# Weather_Shield_V12.net
KiCad netlist of a schematic drawn in EAGLE
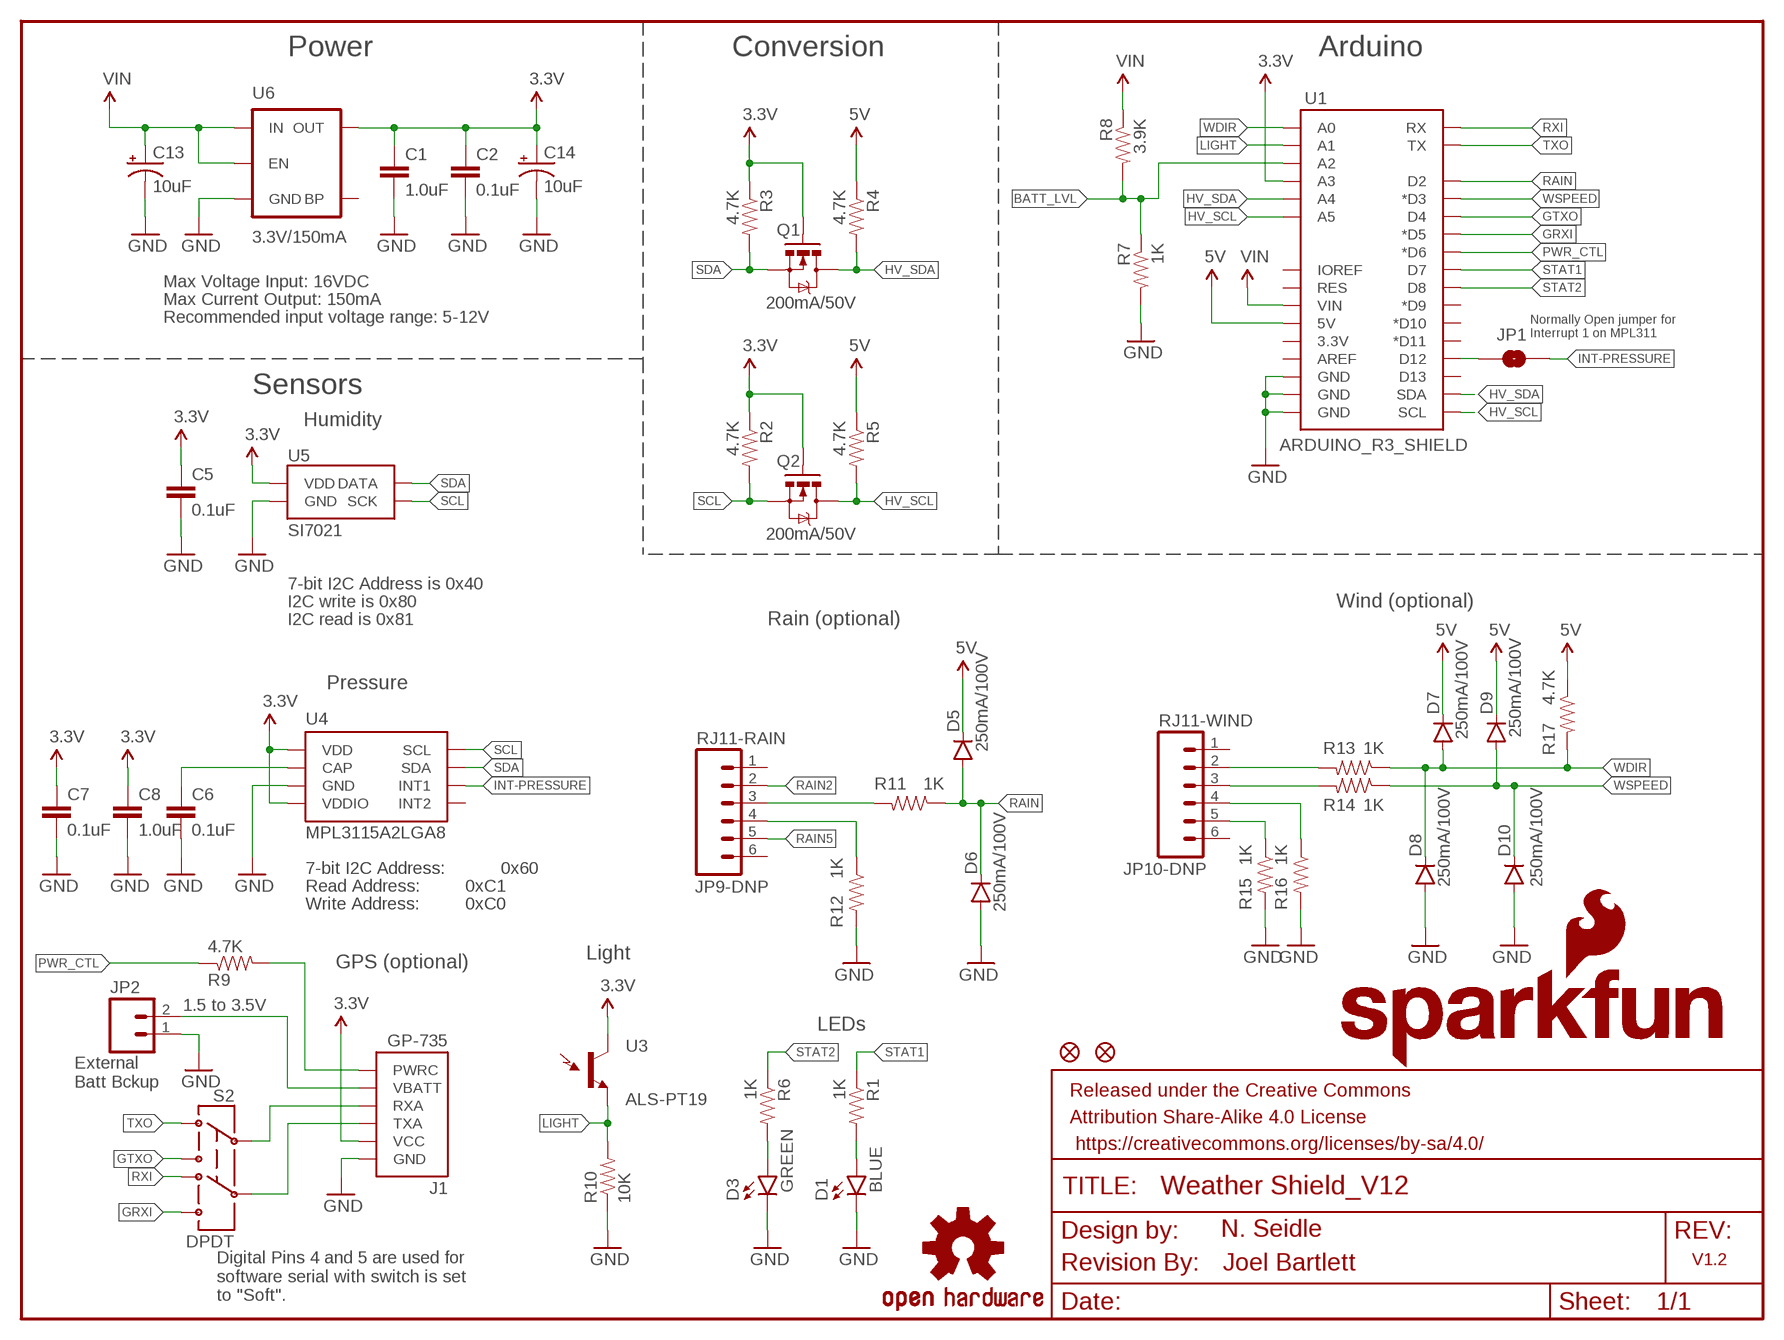
[diagram p0: schematic, sheet 1]

(export (version "E")
  (design (tool "Eeschema 10.0.6"))
  (components
    (comp (ref "C1")
      (value "1.0uF")
      (footprint "eagle-import:0603-CAP")
      (libsource (lib "eagle-import") (part "1.0UF-16V-10%(0603)"))
    )
    (comp (ref "C2")
      (value "0.1uF")
      (footprint "eagle-import:0603-CAP")
      (libsource (lib "eagle-import") (part "0.1UF-25V(+80/-20%)(0603)"))
    )
    (comp (ref "C5")
      (value "0.1uF")
      (footprint "eagle-import:0603-CAP")
      (libsource (lib "eagle-import") (part "0.1UF-25V(+80/-20%)(0603)"))
    )
    (comp (ref "C6")
      (value "0.1uF")
      (footprint "eagle-import:0603-CAP")
      (libsource (lib "eagle-import") (part "0.1UF-25V(+80/-20%)(0603)"))
    )
    (comp (ref "C7")
      (value "0.1uF")
      (footprint "eagle-import:0603-CAP")
      (libsource (lib "eagle-import") (part "0.1UF-25V(+80/-20%)(0603)"))
    )
    (comp (ref "C8")
      (value "1.0uF")
      (footprint "eagle-import:0603-CAP")
      (libsource (lib "eagle-import") (part "1.0UF-16V-10%(0603)"))
    )
    (comp (ref "C13")
      (value "10uF")
      (footprint "eagle-import:EIA3216")
      (libsource (lib "eagle-import") (part "10UF-16V-10%(TANT)"))
    )
    (comp (ref "C14")
      (value "10uF")
      (footprint "eagle-import:EIA3216")
      (libsource (lib "eagle-import") (part "10UF-16V-10%(TANT)"))
    )
    (comp (ref "D1")
      (value "BLUE")
      (footprint "eagle-import:LED-0603")
      (libsource (lib "eagle-import") (part "LED-BLUE0603"))
    )
    (comp (ref "D3")
      (value "GREEN")
      (footprint "eagle-import:LED-0603")
      (libsource (lib "eagle-import") (part "LED-GREEN0603"))
    )
    (comp (ref "D5")
      (value "250mA/100V")
      (footprint "eagle-import:SOD-323")
      (libsource (lib "eagle-import") (part "DIODEBAS16"))
    )
    (comp (ref "D6")
      (value "250mA/100V")
      (footprint "eagle-import:SOD-323")
      (libsource (lib "eagle-import") (part "DIODEBAS16"))
    )
    (comp (ref "D7")
      (value "250mA/100V")
      (footprint "eagle-import:SOD-323")
      (libsource (lib "eagle-import") (part "DIODEBAS16"))
    )
    (comp (ref "D8")
      (value "250mA/100V")
      (footprint "eagle-import:SOD-323")
      (libsource (lib "eagle-import") (part "DIODEBAS16"))
    )
    (comp (ref "D9")
      (value "250mA/100V")
      (footprint "eagle-import:SOD-323")
      (libsource (lib "eagle-import") (part "DIODEBAS16"))
    )
    (comp (ref "D10")
      (value "250mA/100V")
      (footprint "eagle-import:SOD-323")
      (libsource (lib "eagle-import") (part "DIODEBAS16"))
    )
    (comp (ref "FD1")
      (value "FIDUCIAL1X2")
      (footprint "eagle-import:FIDUCIAL-1X2")
      (libsource (lib "eagle-import") (part "FIDUCIAL1X2"))
    )
    (comp (ref "FD2")
      (value "FIDUCIAL1X2")
      (footprint "eagle-import:FIDUCIAL-1X2")
      (libsource (lib "eagle-import") (part "FIDUCIAL1X2"))
    )
    (comp (ref "FRAME1")
      (value "FRAME-LETTER")
      (footprint "eagle-import:CREATIVE_COMMONS")
      (libsource (lib "eagle-import") (part "FRAME-LETTER"))
    )
    (comp (ref "J1")
      (value "GP-735")
      (footprint "eagle-import:GP-635T")
      (libsource (lib "eagle-import") (part "GP-635TSMD"))
    )
    (comp (ref "JP1")
      (value "JUMPER-PAD-2-NO")
      (footprint "eagle-import:PAD-JUMPER-2-NO_NO_SILK")
      (libsource (lib "eagle-import") (part "JUMPER-PAD-2-NO"))
    )
    (comp (ref "JP2")
      (value "External Batt Bckup")
      (footprint "eagle-import:1X02")
      (libsource (lib "eagle-import") (part "M02PTH"))
    )
    (comp (ref "JP9-DNP")
      (value "RJ11-RAIN")
      (footprint "eagle-import:RJ11-6")
      (libsource (lib "eagle-import") (part "RJ11-6PTH"))
    )
    (comp (ref "JP10-DNP")
      (value "RJ11-WIND")
      (footprint "eagle-import:RJ11-6")
      (libsource (lib "eagle-import") (part "RJ11-6PTH"))
    )
    (comp (ref "LOGO1")
      (value "OSHW-LOGOM")
      (footprint "eagle-import:OSHW-LOGO-M")
      (libsource (lib "eagle-import") (part "OSHW-LOGOM"))
    )
    (comp (ref "LOGO2")
      (value "SFE_LOGO_NAME_FLAME.1_INCH")
      (footprint "eagle-import:SFE_LOGO_NAME_FLAME_.1")
      (libsource (lib "eagle-import") (part "SFE_LOGO_NAME_FLAME.1_INCH"))
    )
    (comp (ref "Q1")
      (value "200mA/50V")
      (footprint "eagle-import:SOT23-3")
      (libsource (lib "eagle-import") (part "MOSFET-NCHANNELBSS138"))
    )
    (comp (ref "Q2")
      (value "200mA/50V")
      (footprint "eagle-import:SOT23-3")
      (libsource (lib "eagle-import") (part "MOSFET-NCHANNELBSS138"))
    )
    (comp (ref "R1")
      (value "1K")
      (footprint "eagle-import:0603-RES")
      (libsource (lib "eagle-import") (part "1KOHM-1/10W-1%(0603)"))
    )
    (comp (ref "R2")
      (value "4.7K")
      (footprint "eagle-import:0603-RES")
      (libsource (lib "eagle-import") (part "4.7KOHM-1/10W-1%(0603)"))
    )
    (comp (ref "R3")
      (value "4.7K")
      (footprint "eagle-import:0603-RES")
      (libsource (lib "eagle-import") (part "4.7KOHM-1/10W-1%(0603)"))
    )
    (comp (ref "R4")
      (value "4.7K")
      (footprint "eagle-import:0603-RES")
      (libsource (lib "eagle-import") (part "4.7KOHM-1/10W-1%(0603)"))
    )
    (comp (ref "R5")
      (value "4.7K")
      (footprint "eagle-import:0603-RES")
      (libsource (lib "eagle-import") (part "4.7KOHM-1/10W-1%(0603)"))
    )
    (comp (ref "R6")
      (value "1K")
      (footprint "eagle-import:0603-RES")
      (libsource (lib "eagle-import") (part "1KOHM-1/10W-1%(0603)"))
    )
    (comp (ref "R7")
      (value "1K")
      (footprint "eagle-import:0603-RES")
      (libsource (lib "eagle-import") (part "1KOHM-1/10W-1%(0603)"))
    )
    (comp (ref "R8")
      (value "3.9K")
      (footprint "eagle-import:0603")
      (libsource (lib "eagle-import") (part "3.9KOHM1/10W1%(0603)"))
    )
    (comp (ref "R9")
      (value "4.7K")
      (footprint "eagle-import:0603-RES")
      (libsource (lib "eagle-import") (part "4.7KOHM-1/10W-1%(0603)"))
    )
    (comp (ref "R10")
      (value "10K")
      (footprint "eagle-import:0603-RES")
      (libsource (lib "eagle-import") (part "10KOHM-1/10W-1%(0603)0603"))
    )
    (comp (ref "R11")
      (value "1K")
      (footprint "eagle-import:0603-RES")
      (libsource (lib "eagle-import") (part "1KOHM-1/10W-1%(0603)"))
    )
    (comp (ref "R12")
      (value "1K")
      (footprint "eagle-import:0603-RES")
      (libsource (lib "eagle-import") (part "1KOHM-1/10W-1%(0603)"))
    )
    (comp (ref "R13")
      (value "1K")
      (footprint "eagle-import:0603-RES")
      (libsource (lib "eagle-import") (part "1KOHM-1/10W-1%(0603)"))
    )
    (comp (ref "R14")
      (value "1K")
      (footprint "eagle-import:0603-RES")
      (libsource (lib "eagle-import") (part "1KOHM-1/10W-1%(0603)"))
    )
    (comp (ref "R15")
      (value "1K")
      (footprint "eagle-import:0603-RES")
      (libsource (lib "eagle-import") (part "1KOHM-1/10W-1%(0603)"))
    )
    (comp (ref "R16")
      (value "1K")
      (footprint "eagle-import:0603-RES")
      (libsource (lib "eagle-import") (part "1KOHM-1/10W-1%(0603)"))
    )
    (comp (ref "R17")
      (value "4.7K")
      (footprint "eagle-import:0603-RES")
      (libsource (lib "eagle-import") (part "4.7KOHM-1/10W-1%(0603)"))
    )
    (comp (ref "S2")
      (value "DPDT")
      (footprint "eagle-import:AYZ0202")
      (libsource (lib "eagle-import") (part "SWITCH-DPDTAYZ0202"))
    )
    (comp (ref "U$2")
      (value "REVISION")
      (footprint "eagle-import:REVISION")
      (libsource (lib "eagle-import") (part "REVISION"))
    )
    (comp (ref "U1")
      (value "ARDUINO_R3_SHIELD")
      (footprint "eagle-import:UNO_R3_SHIELD")
      (libsource (lib "eagle-import") (part "ARDUINO_R3_SHIELD"))
    )
    (comp (ref "U3")
      (value "ALS-PT19")
      (footprint "eagle-import:ALS-PT19")
      (libsource (lib "eagle-import") (part "LIGHTSENSORALS"))
    )
    (comp (ref "U4")
      (value "MPL3115A2LGA8")
      (footprint "eagle-import:LGA8")
      (libsource (lib "eagle-import") (part "MPL3115A2LGA8"))
    )
    (comp (ref "U5")
      (value "SI7021")
      (footprint "eagle-import:SI7021")
      (libsource (lib "eagle-import") (part "SI7021"))
    )
    (comp (ref "U6")
      (value "3.3V/150mA")
      (footprint "eagle-import:SOT23-5")
      (libsource (lib "eagle-import") (part "V_REG_MIC52053.3V"))
    )
  )
  (nets
    (net (code "1") (name "3.3V") (class "Default")
      (node (ref "C1") (pin "1") (pinfunction "1_1") (pintype "passive"))
      (node (ref "C14") (pin "A") (pinfunction "+_A") (pintype "passive"))
      (node (ref "C2") (pin "1") (pinfunction "1_1") (pintype "passive"))
      (node (ref "C5") (pin "1") (pinfunction "1_1") (pintype "passive"))
      (node (ref "C7") (pin "1") (pinfunction "1_1") (pintype "passive"))
      (node (ref "C8") (pin "1") (pinfunction "1_1") (pintype "passive"))
      (node (ref "J1") (pin "2") (pinfunction "VCC_2") (pintype "power_in"))
      (node (ref "Q1") (pin "1") (pinfunction "G_1") (pintype "passive"))
      (node (ref "Q2") (pin "1") (pinfunction "G_1") (pintype "passive"))
      (node (ref "R2") (pin "1") (pinfunction "1_1") (pintype "passive"))
      (node (ref "R3") (pin "1") (pinfunction "1_1") (pintype "passive"))
      (node (ref "U1") (pin "A3") (pinfunction "A3_A3") (pintype "bidirectional"))
      (node (ref "U3") (pin "C") (pinfunction "C1_C") (pintype "passive"))
      (node (ref "U4") (pin "1") (pinfunction "VDD_1") (pintype "power_in"))
      (node (ref "U4") (pin "4") (pinfunction "VDDIO_4") (pintype "power_in"))
      (node (ref "U5") (pin "VDD") (pinfunction "VDD_VDD") (pintype "power_in"))
      (node (ref "U6") (pin "5") (pinfunction "OUT_5") (pintype "passive"))
    )
    (net (code "2") (name "5V") (class "Default")
      (node (ref "D5") (pin "C") (pinfunction "C_C") (pintype "passive"))
      (node (ref "D7") (pin "C") (pinfunction "C_C") (pintype "passive"))
      (node (ref "D9") (pin "C") (pinfunction "C_C") (pintype "passive"))
      (node (ref "R17") (pin "1") (pinfunction "1_1") (pintype "passive"))
      (node (ref "R4") (pin "1") (pinfunction "1_1") (pintype "passive"))
      (node (ref "R5") (pin "1") (pinfunction "1_1") (pintype "passive"))
      (node (ref "U1") (pin "5V") (pinfunction "5V_5V") (pintype "bidirectional"))
    )
    (net (code "3") (name "BATT_LVL") (class "Default")
      (node (ref "R7") (pin "1") (pinfunction "1_1") (pintype "passive"))
      (node (ref "R8") (pin "2") (pinfunction "2_2") (pintype "passive"))
      (node (ref "U1") (pin "A2") (pinfunction "A2_A2") (pintype "bidirectional"))
    )
    (net (code "4") (name "GND") (class "Default")
      (node (ref "C1") (pin "2") (pinfunction "2_2") (pintype "passive"))
      (node (ref "C13") (pin "C") (pinfunction "-_C") (pintype "passive"))
      (node (ref "C14") (pin "C") (pinfunction "-_C") (pintype "passive"))
      (node (ref "C2") (pin "2") (pinfunction "2_2") (pintype "passive"))
      (node (ref "C5") (pin "2") (pinfunction "2_2") (pintype "passive"))
      (node (ref "C6") (pin "2") (pinfunction "2_2") (pintype "passive"))
      (node (ref "C7") (pin "2") (pinfunction "2_2") (pintype "passive"))
      (node (ref "C8") (pin "2") (pinfunction "2_2") (pintype "passive"))
      (node (ref "D1") (pin "C") (pinfunction "C_C") (pintype "passive"))
      (node (ref "D10") (pin "A") (pinfunction "A_A") (pintype "passive"))
      (node (ref "D3") (pin "C") (pinfunction "C_C") (pintype "passive"))
      (node (ref "D6") (pin "A") (pinfunction "A_A") (pintype "passive"))
      (node (ref "D8") (pin "A") (pinfunction "A_A") (pintype "passive"))
      (node (ref "J1") (pin "1") (pinfunction "GND_1") (pintype "power_in"))
      (node (ref "JP2") (pin "1") (pinfunction "1_1") (pintype "passive"))
      (node (ref "R10") (pin "1") (pinfunction "1_1") (pintype "passive"))
      (node (ref "R12") (pin "2") (pinfunction "2_2") (pintype "passive"))
      (node (ref "R15") (pin "2") (pinfunction "2_2") (pintype "passive"))
      (node (ref "R16") (pin "2") (pinfunction "2_2") (pintype "passive"))
      (node (ref "R7") (pin "2") (pinfunction "2_2") (pintype "passive"))
      (node (ref "U1") (pin "GND@0") (pinfunction "GND_GND@0") (pintype "bidirectional"))
      (node (ref "U1") (pin "GND@1") (pinfunction "GND_GND@1") (pintype "bidirectional"))
      (node (ref "U1") (pin "GND@2") (pinfunction "GND_GND@2") (pintype "bidirectional"))
      (node (ref "U4") (pin "3") (pinfunction "GND_3") (pintype "power_in"))
      (node (ref "U5") (pin "GND") (pinfunction "GND_GND") (pintype "power_in"))
      (node (ref "U6") (pin "2") (pinfunction "GND_2") (pintype "input"))
    )
    (net (code "5") (name "GRXI") (class "Default")
      (node (ref "S2") (pin "6") (pinfunction "6_6") (pintype "bidirectional"))
      (node (ref "U1") (pin "D5") (pinfunction "*D5_D5") (pintype "bidirectional"))
    )
    (net (code "6") (name "GTXO") (class "Default")
      (node (ref "S2") (pin "3") (pinfunction "3_3") (pintype "bidirectional"))
      (node (ref "U1") (pin "D4") (pinfunction "D4_D4") (pintype "bidirectional"))
    )
    (net (code "7") (name "HV_SCL") (class "Default")
      (node (ref "Q2") (pin "3") (pinfunction "D_3") (pintype "passive"))
      (node (ref "R5") (pin "2") (pinfunction "2_2") (pintype "passive"))
      (node (ref "U1") (pin "A5") (pinfunction "A5_A5") (pintype "bidirectional"))
      (node (ref "U1") (pin "SCL") (pinfunction "SCL_SCL") (pintype "bidirectional"))
    )
    (net (code "8") (name "HV_SDA") (class "Default")
      (node (ref "Q1") (pin "3") (pinfunction "D_3") (pintype "passive"))
      (node (ref "R4") (pin "2") (pinfunction "2_2") (pintype "passive"))
      (node (ref "U1") (pin "A4") (pinfunction "A4_A4") (pintype "bidirectional"))
      (node (ref "U1") (pin "SDA") (pinfunction "SDA_SDA") (pintype "bidirectional"))
    )
    (net (code "9") (name "INT-PRESSURE") (class "Default")
      (node (ref "JP1") (pin "2") (pinfunction "2_2") (pintype "passive"))
      (node (ref "U4") (pin "6") (pinfunction "INT1_6") (pintype "output"))
    )
    (net (code "10") (name "LIGHT") (class "Default")
      (node (ref "R10") (pin "2") (pinfunction "2_2") (pintype "passive"))
      (node (ref "U1") (pin "A1") (pinfunction "A1_A1") (pintype "bidirectional"))
      (node (ref "U3") (pin "E") (pinfunction "E1_E") (pintype "passive"))
    )
    (net (code "11") (name "Net-(D1-PadA)") (class "Default")
      (node (ref "D1") (pin "A") (pinfunction "A_A") (pintype "passive"))
      (node (ref "R1") (pin "2") (pinfunction "2_2") (pintype "passive"))
    )
    (net (code "12") (name "Net-(D3-PadA)") (class "Default")
      (node (ref "D3") (pin "A") (pinfunction "A_A") (pintype "passive"))
      (node (ref "R6") (pin "2") (pinfunction "2_2") (pintype "passive"))
    )
    (net (code "13") (name "Net-(J1-PWRC)") (class "Default")
      (node (ref "J1") (pin "6") (pinfunction "PWRC_6") (pintype "input"))
      (node (ref "R9") (pin "2") (pinfunction "2_2") (pintype "passive"))
    )
    (net (code "14") (name "Net-(J1-RXA)") (class "Default")
      (node (ref "J1") (pin "4") (pinfunction "RXA_4") (pintype "input"))
      (node (ref "S2") (pin "2") (pinfunction "2_2") (pintype "bidirectional"))
    )
    (net (code "15") (name "Net-(J1-TXA)") (class "Default")
      (node (ref "J1") (pin "3") (pinfunction "TXA_3") (pintype "output"))
      (node (ref "S2") (pin "5") (pinfunction "5_5") (pintype "bidirectional"))
    )
    (net (code "16") (name "Net-(J1-VBATT)") (class "Default")
      (node (ref "J1") (pin "5") (pinfunction "VBATT_5") (pintype "power_in"))
      (node (ref "JP2") (pin "2") (pinfunction "2_2") (pintype "passive"))
    )
    (net (code "17") (name "Net-(JP1-Pad1)") (class "Default")
      (node (ref "JP1") (pin "1") (pinfunction "1_1") (pintype "passive"))
      (node (ref "U1") (pin "D12") (pinfunction "D12_D12") (pintype "bidirectional"))
    )
    (net (code "18") (name "Net-(JP9-DNP-Pad3)") (class "Default")
      (node (ref "JP9-DNP") (pin "3") (pinfunction "3_3") (pintype "passive"))
      (node (ref "R11") (pin "2") (pinfunction "2_2") (pintype "passive"))
    )
    (net (code "19") (name "Net-(JP9-DNP-Pad4)") (class "Default")
      (node (ref "JP9-DNP") (pin "4") (pinfunction "4_4") (pintype "passive"))
      (node (ref "R12") (pin "1") (pinfunction "1_1") (pintype "passive"))
    )
    (net (code "20") (name "Net-(JP10-DNP-Pad2)") (class "Default")
      (node (ref "JP10-DNP") (pin "2") (pinfunction "2_2") (pintype "passive"))
      (node (ref "R13") (pin "2") (pinfunction "2_2") (pintype "passive"))
    )
    (net (code "21") (name "Net-(JP10-DNP-Pad3)") (class "Default")
      (node (ref "JP10-DNP") (pin "3") (pinfunction "3_3") (pintype "passive"))
      (node (ref "R14") (pin "2") (pinfunction "2_2") (pintype "passive"))
    )
    (net (code "22") (name "Net-(JP10-DNP-Pad4)") (class "Default")
      (node (ref "JP10-DNP") (pin "4") (pinfunction "4_4") (pintype "passive"))
      (node (ref "R16") (pin "1") (pinfunction "1_1") (pintype "passive"))
    )
    (net (code "23") (name "Net-(JP10-DNP-Pad5)") (class "Default")
      (node (ref "JP10-DNP") (pin "5") (pinfunction "5_5") (pintype "passive"))
      (node (ref "R15") (pin "1") (pinfunction "1_1") (pintype "passive"))
    )
    (net (code "24") (name "Net-(U4-CAP)") (class "Default")
      (node (ref "C6") (pin "1") (pinfunction "1_1") (pintype "passive"))
      (node (ref "U4") (pin "2") (pinfunction "CAP_2") (pintype "power_in"))
    )
    (net (code "25") (name "PWR_CTL") (class "Default")
      (node (ref "R9") (pin "1") (pinfunction "1_1") (pintype "passive"))
      (node (ref "U1") (pin "D6") (pinfunction "*D6_D6") (pintype "bidirectional"))
    )
    (net (code "26") (name "RAIN") (class "Default")
      (node (ref "D5") (pin "A") (pinfunction "A_A") (pintype "passive"))
      (node (ref "D6") (pin "C") (pinfunction "C_C") (pintype "passive"))
      (node (ref "R11") (pin "1") (pinfunction "1_1") (pintype "passive"))
      (node (ref "U1") (pin "D2") (pinfunction "D2_D2") (pintype "bidirectional"))
    )
    (net (code "27") (name "RAIN2") (class "Default")
      (node (ref "JP9-DNP") (pin "2") (pinfunction "2_2") (pintype "passive"))
    )
    (net (code "28") (name "RAIN5") (class "Default")
      (node (ref "JP9-DNP") (pin "5") (pinfunction "5_5") (pintype "passive"))
    )
    (net (code "29") (name "RXI") (class "Default")
      (node (ref "S2") (pin "4") (pinfunction "4_4") (pintype "bidirectional"))
      (node (ref "U1") (pin "RX") (pinfunction "RX_RX") (pintype "bidirectional"))
    )
    (net (code "30") (name "SCL") (class "Default")
      (node (ref "Q2") (pin "2") (pinfunction "S_2") (pintype "passive"))
      (node (ref "R2") (pin "2") (pinfunction "2_2") (pintype "passive"))
      (node (ref "U4") (pin "8") (pinfunction "SCL_8") (pintype "bidirectional"))
      (node (ref "U5") (pin "SCK") (pinfunction "SCK_SCK") (pintype "input"))
    )
    (net (code "31") (name "SDA") (class "Default")
      (node (ref "Q1") (pin "2") (pinfunction "S_2") (pintype "passive"))
      (node (ref "R3") (pin "2") (pinfunction "2_2") (pintype "passive"))
      (node (ref "U4") (pin "7") (pinfunction "SDA_7") (pintype "bidirectional"))
      (node (ref "U5") (pin "DATA") (pinfunction "DATA_DATA") (pintype "bidirectional"))
    )
    (net (code "32") (name "STAT1") (class "Default")
      (node (ref "R1") (pin "1") (pinfunction "1_1") (pintype "passive"))
      (node (ref "U1") (pin "D7") (pinfunction "D7_D7") (pintype "bidirectional"))
    )
    (net (code "33") (name "STAT2") (class "Default")
      (node (ref "R6") (pin "1") (pinfunction "1_1") (pintype "passive"))
      (node (ref "U1") (pin "D8") (pinfunction "D8_D8") (pintype "bidirectional"))
    )
    (net (code "34") (name "TXO") (class "Default")
      (node (ref "S2") (pin "1") (pinfunction "1_1") (pintype "bidirectional"))
      (node (ref "U1") (pin "TX") (pinfunction "TX_TX") (pintype "bidirectional"))
    )
    (net (code "35") (name "VIN") (class "Default")
      (node (ref "C13") (pin "A") (pinfunction "+_A") (pintype "passive"))
      (node (ref "R8") (pin "1") (pinfunction "1_1") (pintype "passive"))
      (node (ref "U1") (pin "VIN") (pinfunction "VIN_VIN") (pintype "bidirectional"))
      (node (ref "U6") (pin "1") (pinfunction "IN_1") (pintype "input"))
      (node (ref "U6") (pin "3") (pinfunction "EN_3") (pintype "input"))
    )
    (net (code "36") (name "WDIR") (class "Default")
      (node (ref "D7") (pin "A") (pinfunction "A_A") (pintype "passive"))
      (node (ref "D8") (pin "C") (pinfunction "C_C") (pintype "passive"))
      (node (ref "R13") (pin "1") (pinfunction "1_1") (pintype "passive"))
      (node (ref "R17") (pin "2") (pinfunction "2_2") (pintype "passive"))
      (node (ref "U1") (pin "A0") (pinfunction "A0_A0") (pintype "bidirectional"))
    )
    (net (code "37") (name "WSPEED") (class "Default")
      (node (ref "D10") (pin "C") (pinfunction "C_C") (pintype "passive"))
      (node (ref "D9") (pin "A") (pinfunction "A_A") (pintype "passive"))
      (node (ref "R14") (pin "1") (pinfunction "1_1") (pintype "passive"))
      (node (ref "U1") (pin "D3") (pinfunction "*D3_D3") (pintype "bidirectional"))
    )
    (net (code "38") (name "unconnected-(JP9-DNP-Pad1)") (class "Default")
      (node (ref "JP9-DNP") (pin "1") (pinfunction "1_1") (pintype "passive"))
    )
    (net (code "39") (name "unconnected-(JP9-DNP-Pad6)") (class "Default")
      (node (ref "JP9-DNP") (pin "6") (pinfunction "6_6") (pintype "passive"))
    )
    (net (code "40") (name "unconnected-(JP10-DNP-Pad1)") (class "Default")
      (node (ref "JP10-DNP") (pin "1") (pinfunction "1_1") (pintype "passive"))
    )
    (net (code "41") (name "unconnected-(JP10-DNP-Pad6)") (class "Default")
      (node (ref "JP10-DNP") (pin "6") (pinfunction "6_6") (pintype "passive"))
    )
    (net (code "42") (name "unconnected-(U1-*D9-PadD9)") (class "Default")
      (node (ref "U1") (pin "D9") (pinfunction "*D9_D9") (pintype "bidirectional"))
    )
    (net (code "43") (name "unconnected-(U1-*D10-PadD10)") (class "Default")
      (node (ref "U1") (pin "D10") (pinfunction "*D10_D10") (pintype "bidirectional"))
    )
    (net (code "44") (name "unconnected-(U1-*D11-PadD11)") (class "Default")
      (node (ref "U1") (pin "D11") (pinfunction "*D11_D11") (pintype "bidirectional"))
    )
    (net (code "45") (name "unconnected-(U1-Pad3.3V)") (class "Default")
      (node (ref "U1") (pin "3.3V") (pinfunction "3.3V_3.3V") (pintype "bidirectional"))
    )
    (net (code "46") (name "unconnected-(U1-PadAREF)") (class "Default")
      (node (ref "U1") (pin "AREF") (pinfunction "AREF_AREF") (pintype "bidirectional"))
    )
    (net (code "47") (name "unconnected-(U1-PadD13)") (class "Default")
      (node (ref "U1") (pin "D13") (pinfunction "D13_D13") (pintype "bidirectional"))
    )
    (net (code "48") (name "unconnected-(U1-PadIOREF)") (class "Default")
      (node (ref "U1") (pin "IOREF") (pinfunction "IOREF_IOREF") (pintype "bidirectional"))
    )
    (net (code "49") (name "unconnected-(U1-PadRES)") (class "Default")
      (node (ref "U1") (pin "RES") (pinfunction "RES_RES") (pintype "bidirectional"))
    )
    (net (code "50") (name "unconnected-(U4-INT2-Pad5)") (class "Default")
      (node (ref "U4") (pin "5") (pinfunction "INT2_5") (pintype "output"))
    )
    (net (code "51") (name "unconnected-(U6-BP-Pad4)") (class "Default")
      (node (ref "U6") (pin "4") (pinfunction "BP_4") (pintype "input"))
    )
  )
)
